# 8_SATA_TFCARD.net
KiCad netlist of a schematic drawn in Altium Designer
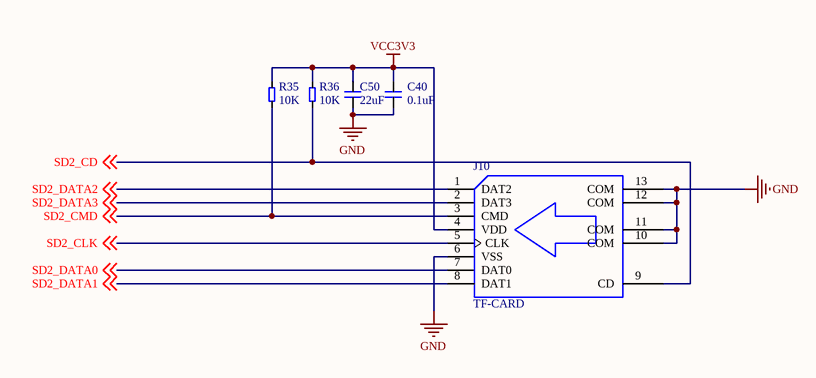
[diagram p0: 8.SATA&TFCARD.SchDoc]

(export (version "E")
  (design (tool "Eeschema 10.0.6"))
  (components
    (comp (ref "C40")
      (value "0.1uF")
      (footprint "0603C")
      (description "电容")
      (libsource (lib "*") (part "电容"))
    )
    (comp (ref "C50") (value "22uF") (footprint "0603C") (description "电容") (libsource (lib "*") (part "电容")))
    (comp (ref "J10") (value "TF-CARD") (footprint "TF-CARD") (libsource (lib "LDT-SCH") (part "TF-CARD")))
    (comp (ref "R35")
      (value "10K")
      (footprint "0603R")
      (description "电阻")
      (libsource (lib "LDT-SCH") (part "电阻"))
    )
    (comp (ref "R36")
      (value "10K")
      (footprint "0603R")
      (description "电阻")
      (libsource (lib "LDT-SCH") (part "电阻"))
    )
  )
  (nets
    (net (code "1") (name "GND") (class "Default")
      (node (ref "C40") (pin "1") (pintype "passive"))
      (node (ref "C50") (pin "1") (pintype "passive"))
      (node (ref "J10") (pin "10") (pinfunction "COM_10") (pintype "passive"))
      (node (ref "J10") (pin "11") (pinfunction "COM_11") (pintype "passive"))
      (node (ref "J10") (pin "12") (pinfunction "COM_12") (pintype "passive"))
      (node (ref "J10") (pin "13") (pinfunction "COM_13") (pintype "passive"))
      (node (ref "J10") (pin "6") (pinfunction "VSS_6") (pintype "passive"))
    )
    (net (code "2") (name "SD2_CD") (class "Default")
      (node (ref "J10") (pin "9") (pinfunction "CD_9") (pintype "passive"))
      (node (ref "R36") (pin "1") (pintype "passive"))
    )
    (net (code "3") (name "SD2_CLK") (class "Default")
      (node (ref "J10") (pin "5") (pinfunction "CLK_5") (pintype "passive"))
    )
    (net (code "4") (name "SD2_CMD") (class "Default")
      (node (ref "J10") (pin "3") (pinfunction "CMD_3") (pintype "passive"))
      (node (ref "R35") (pin "1") (pintype "passive"))
    )
    (net (code "5") (name "SD2_DATA0") (class "Default")
      (node (ref "J10") (pin "7") (pinfunction "DAT0_7") (pintype "passive"))
    )
    (net (code "6") (name "SD2_DATA1") (class "Default")
      (node (ref "J10") (pin "8") (pinfunction "DAT1_8") (pintype "passive"))
    )
    (net (code "7") (name "SD2_DATA2") (class "Default")
      (node (ref "J10") (pin "1") (pinfunction "DAT2_1") (pintype "passive"))
    )
    (net (code "8") (name "SD2_DATA3") (class "Default")
      (node (ref "J10") (pin "2") (pinfunction "DAT3_2") (pintype "passive"))
    )
    (net (code "9") (name "VCC3V3") (class "Default")
      (node (ref "C40") (pin "2") (pintype "passive"))
      (node (ref "C50") (pin "2") (pintype "passive"))
      (node (ref "J10") (pin "4") (pinfunction "VDD_4") (pintype "passive"))
      (node (ref "R35") (pin "2") (pintype "passive"))
      (node (ref "R36") (pin "2") (pintype "passive"))
    )
  )
)
